# EasyEDA_schema.net
KiCad netlist of a schematic drawn in EasyEDA
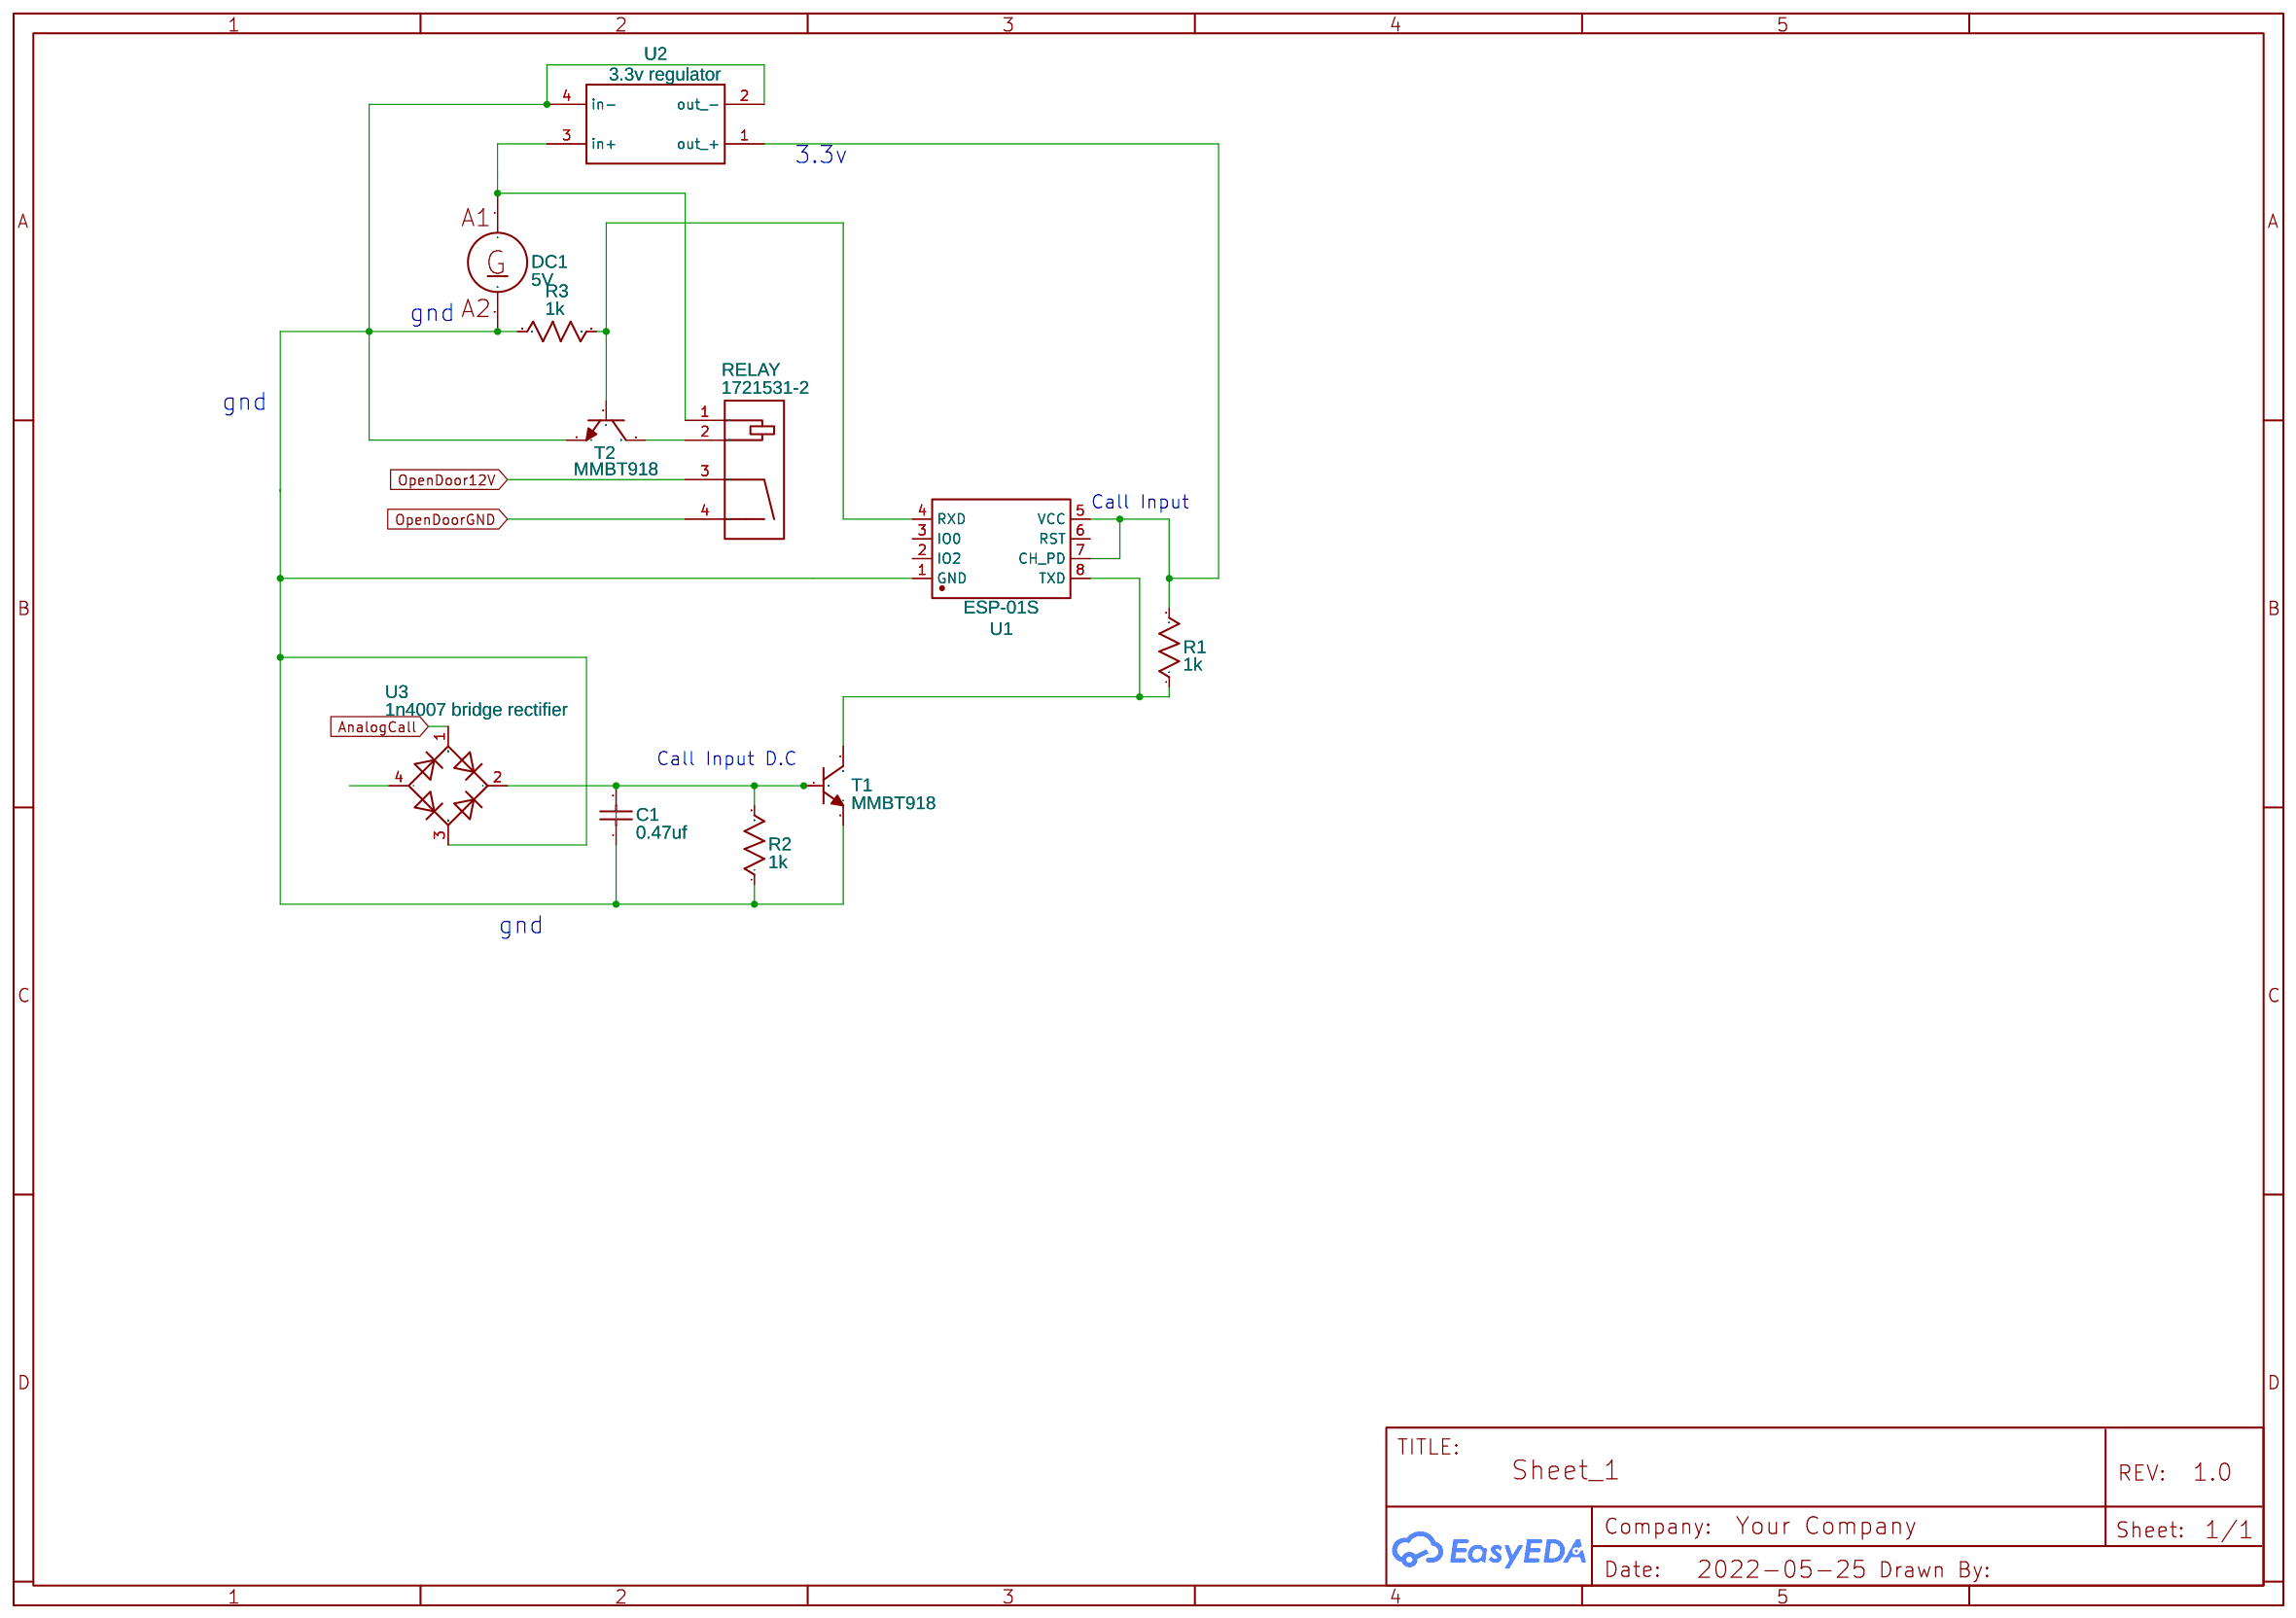
[diagram p0: schematic sheet]

(export (version "E")
  (design (tool "Eeschema 10.0.6"))
  (components
    (comp (ref "C1")
      (value "0.47uf")
      (fields
        (field (name "BOM_Manufacturer Part") "BFC241674704")
        (field (name "BOM_Supplier Part") "E54367")
      )
      (libsource (lib "") (part "0.47uf"))
    )
    (comp (ref "DC1") (value "5V") (libsource (lib "") (part "DC generator 1")))
    (comp (ref "R1") (value "1k") (libsource (lib "") (part "R_0603_US")))
    (comp (ref "R2") (value "1k") (libsource (lib "") (part "R_0603_US")))
    (comp (ref "R3") (value "1k") (libsource (lib "") (part "R_0603_US_1")))
    (comp (ref "RELAY")
      (value "1721531-2")
      (fields (field (name "BOM_Supplier Part") "C355422"))
      (libsource (lib "") (part "1721531-2"))
    )
    (comp (ref "T1")
      (value "MMBT918")
      (fields (field (name "BOM_Supplier Part") "C184118"))
      (libsource (lib "") (part "MMBT918_1"))
    )
    (comp (ref "T2")
      (value "MMBT918")
      (fields (field (name "BOM_Supplier Part") "C184118"))
      (libsource (lib "") (part "MMBT918"))
    )
    (comp (ref "U1")
      (value "ESP-01S")
      (fields (field (name "BOM_Supplier Part") "C111009"))
      (libsource (lib "") (part "ESP-01S"))
    )
    (comp (ref "U2") (value "3.3v regulator") (libsource (lib "") (part "3.3v regulator")))
    (comp (ref "U3") (value "1n4007 bridge rectifier") (libsource (lib "") (part "1n4007 bridge rectifier")))
  )
  (nets
    (net (code "1") (name "AnalogCall") (class "Default")
      (node (ref "U3") (pin "1") (pinfunction "C1_1") (pintype "unspecified"))
    )
    (net (code "2") (name "Net-(T1-B)") (class "Default")
      (node (ref "C1") (pin "2") (pinfunction "2_2") (pintype "input"))
      (node (ref "R2") (pin "2") (pinfunction "2_2") (pintype "unspecified"))
      (node (ref "T1") (pin "1") (pinfunction "B_1") (pintype "unspecified"))
      (node (ref "U3") (pin "2") (pinfunction "+_2") (pintype "unspecified"))
    )
    (net (code "3") (name "Net-(T1-C)") (class "Default")
      (node (ref "R1") (pin "1") (pinfunction "1_1") (pintype "unspecified"))
      (node (ref "T1") (pin "3") (pinfunction "C_3") (pintype "unspecified"))
      (node (ref "U1") (pin "8") (pinfunction "TXD_8") (pintype "unspecified"))
    )
    (net (code "4") (name "Net-(T1-E)") (class "Default")
      (node (ref "C1") (pin "1") (pinfunction "1_1") (pintype "input"))
      (node (ref "DC1") (pin "2") (pinfunction "2_2") (pintype "unspecified"))
      (node (ref "R2") (pin "1") (pinfunction "1_1") (pintype "unspecified"))
      (node (ref "R3") (pin "1") (pinfunction "1_1") (pintype "unspecified"))
      (node (ref "T1") (pin "2") (pinfunction "E_2") (pintype "unspecified"))
      (node (ref "T2") (pin "2") (pinfunction "E_2") (pintype "unspecified"))
      (node (ref "U1") (pin "1") (pinfunction "GND_1") (pintype "unspecified"))
      (node (ref "U2") (pin "2") (pinfunction "out_-_2") (pintype "unspecified"))
      (node (ref "U2") (pin "4") (pinfunction "in-_4") (pintype "unspecified"))
      (node (ref "U3") (pin "3") (pinfunction "C2_3") (pintype "unspecified"))
    )
    (net (code "5") (name "Net-(T2-B)") (class "Default")
      (node (ref "R3") (pin "2") (pinfunction "2_2") (pintype "unspecified"))
      (node (ref "T2") (pin "1") (pinfunction "B_1") (pintype "unspecified"))
      (node (ref "U1") (pin "4") (pinfunction "RXD_4") (pintype "unspecified"))
    )
    (net (code "6") (name "Net-(T2-C)") (class "Default")
      (node (ref "RELAY") (pin "2") (pinfunction "2_2") (pintype "unspecified"))
      (node (ref "T2") (pin "3") (pinfunction "C_3") (pintype "unspecified"))
    )
    (net (code "7") (name "Net-(U1-CH_PD)") (class "Default")
      (node (ref "R1") (pin "2") (pinfunction "2_2") (pintype "unspecified"))
      (node (ref "U1") (pin "5") (pinfunction "VCC_5") (pintype "unspecified"))
      (node (ref "U1") (pin "7") (pinfunction "CH_PD_7") (pintype "unspecified"))
      (node (ref "U2") (pin "1") (pinfunction "out_+_1") (pintype "unspecified"))
    )
    (net (code "8") (name "Net-(U2-in+)") (class "Default")
      (node (ref "DC1") (pin "1") (pinfunction "1_1") (pintype "unspecified"))
      (node (ref "RELAY") (pin "1") (pinfunction "1_1") (pintype "unspecified"))
      (node (ref "U2") (pin "3") (pinfunction "in+_3") (pintype "unspecified"))
    )
    (net (code "9") (name "OpenDoor12V") (class "Default")
      (node (ref "RELAY") (pin "3") (pinfunction "3_3") (pintype "unspecified"))
    )
    (net (code "10") (name "OpenDoorGND") (class "Default")
      (node (ref "RELAY") (pin "4") (pinfunction "4_4") (pintype "unspecified"))
    )
    (net (code "11") (name "unconnected-(U1-IO0-Pad3)") (class "Default")
      (node (ref "U1") (pin "3") (pinfunction "IO0_3") (pintype "unspecified"))
    )
    (net (code "12") (name "unconnected-(U1-IO2-Pad2)") (class "Default")
      (node (ref "U1") (pin "2") (pinfunction "IO2_2") (pintype "unspecified"))
    )
    (net (code "13") (name "unconnected-(U1-RST-Pad6)") (class "Default")
      (node (ref "U1") (pin "6") (pinfunction "RST_6") (pintype "unspecified"))
    )
    (net (code "14") (name "unconnected-(U3---Pad4)") (class "Default")
      (node (ref "U3") (pin "4") (pinfunction "-_4") (pintype "unspecified"))
    )
  )
)
